# PERSEUS.net
KiCad netlist of a schematic drawn in Altium Designer
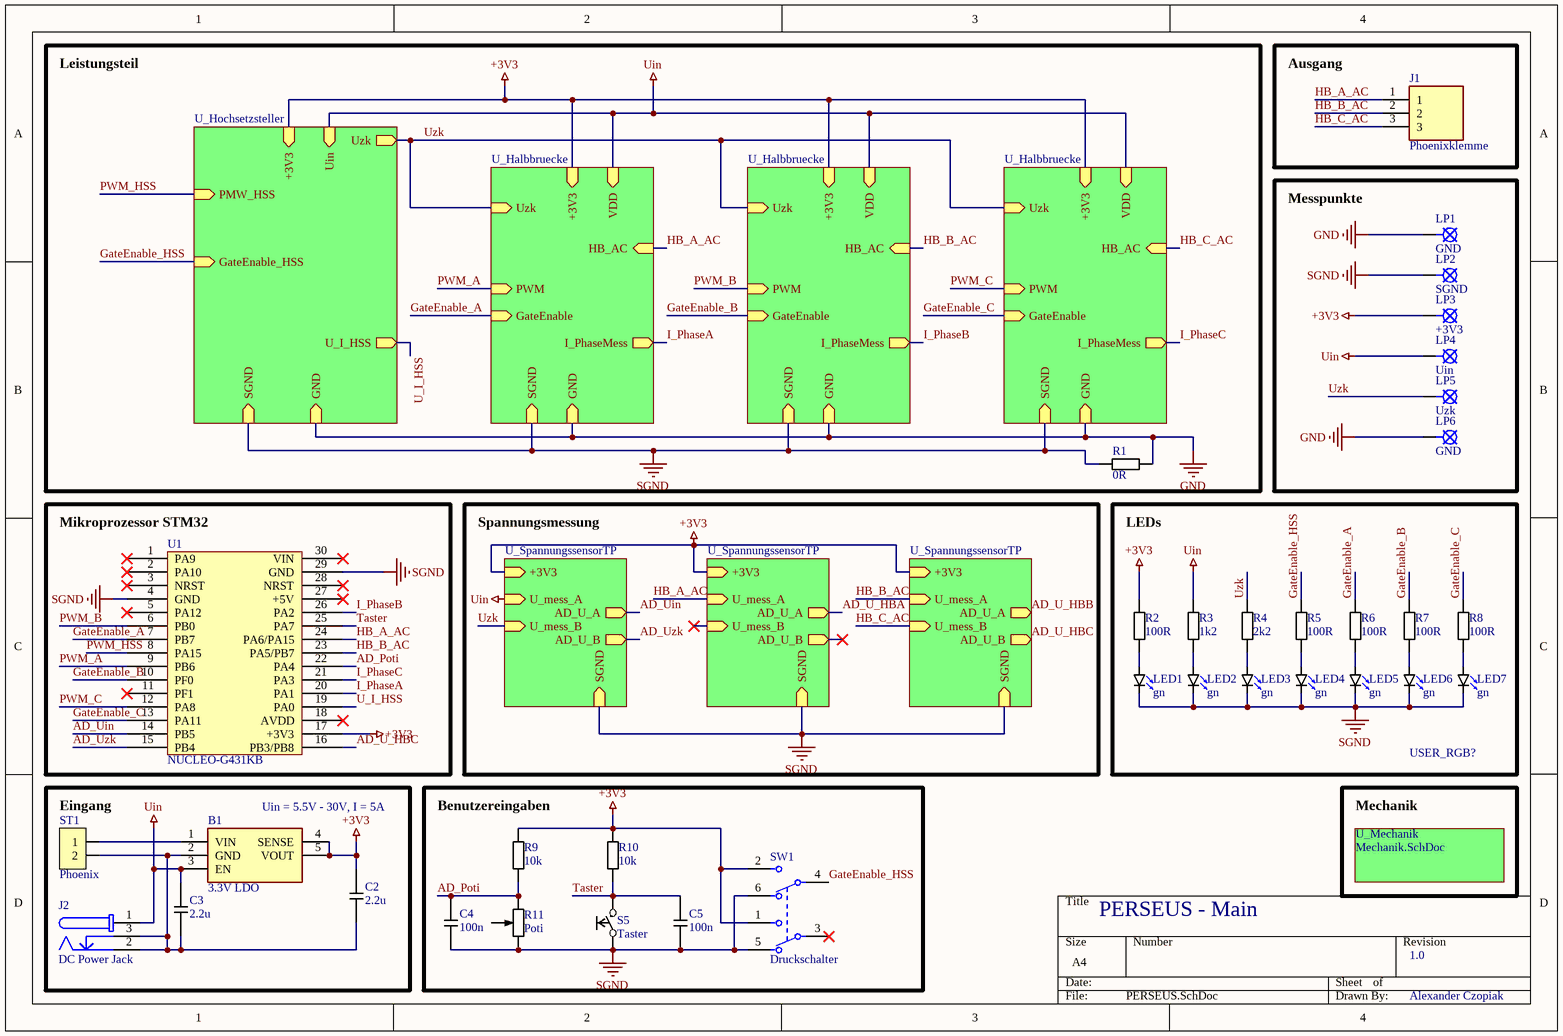
[diagram p0: PERSEUS.SchDoc]

(export (version "E")
  (design (tool "Eeschema 10.0.6"))
  (components
    (comp (ref "B1")
      (value "3.3V LDO")
      (footprint "SOT95P280X100-5N")
      (description "40V, 200mA, Low Noise, CMOS LDO Linear Regulator, ADPL44002AUJZ-3.3-R7")
      (fields
        (field (name "MOUSER PART NUMBER") "584-PL44002AUJZ33R7")
        (field (name "MANUFACTURER_PART_NUMBER") "ADPL44002AUJZ-3.3-R7")
      )
      (libsource (lib "PERSEUS_Parts") (part "Spannungsregler"))
    )
    (comp (ref "C2")
      (value "2.2u")
      (footprint "1206_C")
      (description "Min 2.2uF")
      (libsource (lib "HSLS_Parts") (part "CAP"))
    )
    (comp (ref "C3")
      (value "2.2u")
      (footprint "1206_C")
      (description "Min 2.2uF")
      (libsource (lib "HSLS_Parts") (part "CAP"))
    )
    (comp (ref "C4")
      (value "100n")
      (footprint "1206_C")
      (description "Kondensator (ohne Polarität)")
      (libsource (lib "HSLS_Parts") (part "CAP"))
    )
    (comp (ref "C5")
      (value "100n")
      (footprint "1206_C")
      (description "Kondensator (ohne Polarität)")
      (libsource (lib "HSLS_Parts") (part "CAP"))
    )
    (comp (ref "J1")
      (value "Phoenixklemme")
      (footprint "Phoenix_3er")
      (description "Phoenix: Fixed Terminal Blocks 3P 7.5mm GMKDS 1,5/ 3")
      (fields
        (field (name "MANUFACTURER_PART_NUMBER") "1717033")
        (field (name "MOUSER PART NUMBER") "651-1717033")
      )
      (libsource (lib "PERSEUS_Parts") (part "Leiterbahnklemme"))
    )
    (comp (ref "J2")
      (value "DC Power Jack")
      (footprint "694106301002")
      (libsource (lib "Altium Content Vault") (part "DC Power Jack"))
    )
    (comp (ref "LED1")
      (value "gn")
      (footprint "0805_DI_gr")
      (description "LED SMD 0805 (gruen)")
      (libsource (lib "HSLS_Parts") (part "LED SMD 0805"))
    )
    (comp (ref "LED2")
      (value "gn")
      (footprint "0805_DI_gr")
      (description "LED SMD 0805 (gruen)")
      (libsource (lib "HSLS_Parts") (part "LED SMD 0805"))
    )
    (comp (ref "LED3")
      (value "gn")
      (footprint "0805_DI_gr")
      (description "LED SMD 0805 (gruen)")
      (libsource (lib "HSLS_Parts") (part "LED SMD 0805"))
    )
    (comp (ref "LED4")
      (value "gn")
      (footprint "0805_DI_gr")
      (description "LED SMD 0805 (gruen)")
      (libsource (lib "HSLS_Parts") (part "LED SMD 0805"))
    )
    (comp (ref "LED5")
      (value "gn")
      (footprint "0805_DI_gr")
      (description "LED SMD 0805 (gruen)")
      (libsource (lib "HSLS_Parts") (part "LED SMD 0805"))
    )
    (comp (ref "LED6")
      (value "gn")
      (footprint "0805_DI_gr")
      (description "LED SMD 0805 (gruen)")
      (libsource (lib "HSLS_Parts") (part "LED SMD 0805"))
    )
    (comp (ref "LED7")
      (value "gn")
      (footprint "0805_DI_gr")
      (description "LED SMD 0805 (gruen)")
      (libsource (lib "HSLS_Parts") (part "LED SMD 0805"))
    )
    (comp (ref "LP1") (value "GND") (footprint "LP1") (libsource (lib "HSLS_Parts") (part "LP")))
    (comp (ref "LP2") (value "SGND") (footprint "LP1") (libsource (lib "HSLS_Parts") (part "LP")))
    (comp (ref "LP3") (value "+3V3") (footprint "LP1") (libsource (lib "HSLS_Parts") (part "LP")))
    (comp (ref "LP4") (value "Uin") (footprint "LP1") (libsource (lib "HSLS_Parts") (part "LP")))
    (comp (ref "LP5") (value "Uzk") (footprint "LP1") (libsource (lib "HSLS_Parts") (part "LP")))
    (comp (ref "LP6") (value "GND") (footprint "LP1") (libsource (lib "HSLS_Parts") (part "LP")))
    (comp (ref "R1")
      (value "0R")
      (footprint "1206_R")
      (description "LED Vorwiderstand: Min 65 Ohm, Berechnet für 3.3V, 2V Spannungsabfall, 20mA Strom")
      (libsource (lib "") (part "WIDERSTAND_1"))
    )
    (comp (ref "R2")
      (value "100R")
      (footprint "1206_R")
      (description "LED Vorwiderstand: Min 65 Ohm, Berechnet für 3.3V, 2V Spannungsabfall, 20mA Strom")
      (libsource (lib "HSLS_Parts") (part "WIDERSTAND"))
    )
    (comp (ref "R3")
      (value "1k2")
      (footprint "1206_R")
      (description "LED Vorwiderstand: Min 1.4 kOhm Berechnet für 30V Uin und 2 V Spannungsabfall und If=20mA")
      (libsource (lib "HSLS_Parts") (part "WIDERSTAND"))
    )
    (comp (ref "R4")
      (value "2k2")
      (footprint "1206_R")
      (description "Widerstand")
      (libsource (lib "HSLS_Parts") (part "WIDERSTAND"))
    )
    (comp (ref "R5")
      (value "100R")
      (footprint "1206_R")
      (description "Widerstand")
      (libsource (lib "HSLS_Parts") (part "WIDERSTAND"))
    )
    (comp (ref "R6")
      (value "100R")
      (footprint "1206_R")
      (description "Widerstand")
      (libsource (lib "HSLS_Parts") (part "WIDERSTAND"))
    )
    (comp (ref "R7")
      (value "100R")
      (footprint "1206_R")
      (description "LED Vorwiderstand: Min 65 Ohm, Berechnet für 3.3V, 2V Spannungsabfall, 20mA Strom")
      (libsource (lib "HSLS_Parts") (part "WIDERSTAND"))
    )
    (comp (ref "R8")
      (value "100R")
      (footprint "1206_R")
      (description "LED Vorwiderstand: Min 65 Ohm, Berechnet für 3.3V, 2V Spannungsabfall, 20mA Strom")
      (libsource (lib "HSLS_Parts") (part "WIDERSTAND"))
    )
    (comp (ref "R9")
      (value "10k")
      (footprint "1206_R")
      (description "LED Vorwiderstand: Min 1.4 kOhm Berechnet für 30V Uin und 2 V Spannungsabfall und If=20mA")
      (libsource (lib "HSLS_Parts") (part "WIDERSTAND"))
    )
    (comp (ref "R10")
      (value "10k")
      (footprint "1206_R")
      (description "LED Vorwiderstand: Min 1.4 kOhm Berechnet für 30V Uin und 2 V Spannungsabfall und If=20mA")
      (libsource (lib "HSLS_Parts") (part "WIDERSTAND"))
    )
    (comp (ref "R11")
      (value "Poti")
      (footprint "POT_T607_3D")
      (description "Widerstand")
      (libsource (lib "HSLS_Parts") (part "POT"))
    )
    (comp (ref "S5")
      (value "Taster")
      (footprint "TASTERSMD_3D")
      (libsource (lib "HSLS_Parts") (part "TASTER-SMD"))
    )
    (comp (ref "ST1")
      (value "Phoenix")
      (footprint "MKDS 1,5/ 2")
      (description "Phönix-Klemme")
      (libsource (lib "HSLS_Parts") (part "CONN02"))
    )
    (comp (ref "SW1")
      (value "Druckschalter")
      (footprint "FP-ESB-33133-MFG")
      (description "SWITCH PUSH DPDT 0.2A 14V")
      (libsource (lib "Altium Content Vault") (part "c2a961280ed03fe855f28de6b03a4b6"))
    )
    (comp (ref "U1")
      (value "NUCLEO-G431KB")
      (footprint "NUCLEO-G431KB")
      (libsource (lib "PERSEUS_Parts") (part "NUCLEO-G431KB"))
    )
  )
  (nets
    (net (code "1") (name "+3V3") (class "Default")
      (node (ref "B1") (pin "4") (pinfunction "SENSE_4") (pintype "passive"))
      (node (ref "B1") (pin "5") (pinfunction "VOUT_5") (pintype "passive"))
      (node (ref "C2") (pin "2") (pinfunction "2_2") (pintype "passive"))
      (node (ref "LP3") (pin "1") (pinfunction "1_1") (pintype "passive"))
      (node (ref "R10") (pin "2") (pinfunction "2_2") (pintype "passive"))
      (node (ref "R2") (pin "2") (pinfunction "2_2") (pintype "passive"))
      (node (ref "R9") (pin "2") (pinfunction "2_2") (pintype "passive"))
      (node (ref "SW1") (pin "1") (pinfunction "1_NO_1") (pintype "passive"))
      (node (ref "SW1") (pin "2") (pinfunction "2_NO_2") (pintype "passive"))
      (node (ref "U1") (pin "17") (pinfunction "+3V3_17") (pintype "passive"))
    )
    (net (code "3") (name "/AD_Poti") (class "Default")
      (node (ref "C4") (pin "2") (pinfunction "2_2") (pintype "passive"))
      (node (ref "R11") (pin "2") (pintype "passive"))
      (node (ref "R9") (pin "1") (pinfunction "1_1") (pintype "passive"))
      (node (ref "U1") (pin "22") (pinfunction "PA4_22") (pintype "passive"))
    )
    (net (code "6") (name "/AD_U_HBC") (class "Default")
      (node (ref "U1") (pin "16") (pinfunction "PB3/PB8_16") (pintype "passive"))
    )
    (net (code "7") (name "/AD_Uin") (class "Default")
      (node (ref "U1") (pin "14") (pinfunction "PB5_14") (pintype "passive"))
    )
    (net (code "8") (name "/AD_Uzk") (class "Default")
      (node (ref "U1") (pin "15") (pinfunction "PB4_15") (pintype "passive"))
    )
    (net (code "9") (name "/GateEnable_A") (class "Default")
      (node (ref "R6") (pin "2") (pinfunction "2_2") (pintype "passive"))
      (node (ref "U1") (pin "7") (pinfunction "PB7_7") (pintype "passive"))
    )
    (net (code "10") (name "/GateEnable_B") (class "Default")
      (node (ref "R7") (pin "2") (pinfunction "2_2") (pintype "passive"))
      (node (ref "U1") (pin "10") (pinfunction "PF0_10") (pintype "passive"))
    )
    (net (code "11") (name "/GateEnable_C") (class "Default")
      (node (ref "R8") (pin "2") (pinfunction "2_2") (pintype "passive"))
      (node (ref "U1") (pin "13") (pinfunction "PA11_13") (pintype "passive"))
    )
    (net (code "12") (name "/GateEnable_HSS") (class "Default")
      (node (ref "R5") (pin "2") (pinfunction "2_2") (pintype "passive"))
      (node (ref "SW1") (pin "4") (pinfunction "2_C_4") (pintype "passive"))
    )
    (net (code "13") (name "/HB_A_AC") (class "Default")
      (node (ref "J1") (pin "1") (pinfunction "1_1") (pintype "passive"))
      (node (ref "U1") (pin "24") (pinfunction "PA6/PA15_24") (pintype "passive"))
    )
    (net (code "14") (name "/HB_B_AC") (class "Default")
      (node (ref "J1") (pin "2") (pinfunction "2_2") (pintype "passive"))
      (node (ref "U1") (pin "23") (pinfunction "PA5/PB7_23") (pintype "passive"))
    )
    (net (code "15") (name "/HB_C_AC") (class "Default")
      (node (ref "J1") (pin "3") (pinfunction "3_3") (pintype "passive"))
    )
    (net (code "16") (name "/I_PhaseA") (class "Default")
      (node (ref "U1") (pin "20") (pinfunction "PA1_20") (pintype "passive"))
    )
    (net (code "17") (name "/I_PhaseB") (class "Default")
      (node (ref "U1") (pin "26") (pinfunction "PA2_26") (pintype "passive"))
    )
    (net (code "18") (name "/I_PhaseC") (class "Default")
      (node (ref "U1") (pin "21") (pinfunction "PA3_21") (pintype "passive"))
    )
    (net (code "19") (name "/PWM_A") (class "Default")
      (node (ref "U1") (pin "9") (pinfunction "PB6_9") (pintype "passive"))
    )
    (net (code "20") (name "/PWM_B") (class "Default")
      (node (ref "U1") (pin "6") (pinfunction "PB0_6") (pintype "passive"))
    )
    (net (code "21") (name "/PWM_C") (class "Default")
      (node (ref "U1") (pin "12") (pinfunction "PA8_12") (pintype "passive"))
    )
    (net (code "22") (name "/PWM_HSS") (class "Default")
      (node (ref "U1") (pin "8") (pinfunction "PA15_8") (pintype "passive"))
    )
    (net (code "23") (name "/Taster") (class "Default")
      (node (ref "C5") (pin "2") (pinfunction "2_2") (pintype "passive"))
      (node (ref "R10") (pin "1") (pinfunction "1_1") (pintype "passive"))
      (node (ref "S5") (pin "1") (pinfunction "1_1") (pintype "passive"))
      (node (ref "U1") (pin "25") (pinfunction "PA7_25") (pintype "passive"))
    )
    (net (code "24") (name "/U_I_HSS") (class "Default")
      (node (ref "U1") (pin "19") (pinfunction "PA0_19") (pintype "passive"))
    )
    (net (code "26") (name "/Uzk") (class "Default")
      (node (ref "LP5") (pin "1") (pinfunction "1_1") (pintype "passive"))
      (node (ref "R4") (pin "2") (pinfunction "2_2") (pintype "passive"))
    )
    (net (code "27") (name "GND") (class "Default")
      (node (ref "LP1") (pin "1") (pinfunction "1_1") (pintype "passive"))
      (node (ref "LP6") (pin "1") (pinfunction "1_1") (pintype "passive"))
      (node (ref "R1") (pin "1") (pinfunction "1_1") (pintype "passive"))
    )
    (net (code "28") (name "Net-(B1-GND)") (class "Default")
      (node (ref "B1") (pin "2") (pinfunction "GND_2") (pintype "passive"))
      (node (ref "C2") (pin "1") (pinfunction "1_1") (pintype "passive"))
      (node (ref "C3") (pin "1") (pinfunction "1_1") (pintype "passive"))
      (node (ref "J2") (pin "2") (pinfunction "2_2") (pintype "passive"))
      (node (ref "J2") (pin "3") (pinfunction "3_3") (pintype "passive"))
      (node (ref "ST1") (pin "2") (pinfunction "2_2") (pintype "passive"))
    )
    (net (code "29") (name "Net-(B1-VIN)") (class "Default")
      (node (ref "B1") (pin "1") (pinfunction "VIN_1") (pintype "passive"))
      (node (ref "ST1") (pin "1") (pinfunction "1_1") (pintype "passive"))
    )
    (net (code "30") (name "Net-(LED1-A)") (class "Default")
      (node (ref "LED1") (pin "1") (pinfunction "A_1") (pintype "passive"))
      (node (ref "R2") (pin "1") (pinfunction "1_1") (pintype "passive"))
    )
    (net (code "31") (name "Net-(LED2-A)") (class "Default")
      (node (ref "LED2") (pin "1") (pinfunction "A_1") (pintype "passive"))
      (node (ref "R3") (pin "1") (pinfunction "1_1") (pintype "passive"))
    )
    (net (code "32") (name "Net-(LED3-A)") (class "Default")
      (node (ref "LED3") (pin "1") (pinfunction "A_1") (pintype "passive"))
      (node (ref "R4") (pin "1") (pinfunction "1_1") (pintype "passive"))
    )
    (net (code "33") (name "Net-(LED4-A)") (class "Default")
      (node (ref "LED4") (pin "1") (pinfunction "A_1") (pintype "passive"))
      (node (ref "R5") (pin "1") (pinfunction "1_1") (pintype "passive"))
    )
    (net (code "34") (name "Net-(LED5-A)") (class "Default")
      (node (ref "LED5") (pin "1") (pinfunction "A_1") (pintype "passive"))
      (node (ref "R6") (pin "1") (pinfunction "1_1") (pintype "passive"))
    )
    (net (code "35") (name "Net-(LED6-A)") (class "Default")
      (node (ref "LED6") (pin "1") (pinfunction "A_1") (pintype "passive"))
      (node (ref "R7") (pin "1") (pinfunction "1_1") (pintype "passive"))
    )
    (net (code "36") (name "Net-(LED7-A)") (class "Default")
      (node (ref "LED7") (pin "1") (pinfunction "A_1") (pintype "passive"))
      (node (ref "R8") (pin "1") (pinfunction "1_1") (pintype "passive"))
    )
    (net (code "37") (name "SGND") (class "Default")
      (node (ref "C4") (pin "1") (pinfunction "1_1") (pintype "passive"))
      (node (ref "C5") (pin "1") (pinfunction "1_1") (pintype "passive"))
      (node (ref "LED1") (pin "2") (pinfunction "K_2") (pintype "passive"))
      (node (ref "LED2") (pin "2") (pinfunction "K_2") (pintype "passive"))
      (node (ref "LED3") (pin "2") (pinfunction "K_2") (pintype "passive"))
      (node (ref "LED4") (pin "2") (pinfunction "K_2") (pintype "passive"))
      (node (ref "LED5") (pin "2") (pinfunction "K_2") (pintype "passive"))
      (node (ref "LED6") (pin "2") (pinfunction "K_2") (pintype "passive"))
      (node (ref "LED7") (pin "2") (pinfunction "K_2") (pintype "passive"))
      (node (ref "LP2") (pin "1") (pinfunction "1_1") (pintype "passive"))
      (node (ref "R1") (pin "2") (pinfunction "2_2") (pintype "passive"))
      (node (ref "R11") (pin "1") (pintype "passive"))
      (node (ref "S5") (pin "2") (pinfunction "2_2") (pintype "passive"))
      (node (ref "SW1") (pin "5") (pinfunction "1_NC_5") (pintype "passive"))
      (node (ref "SW1") (pin "6") (pinfunction "2_NC_6") (pintype "passive"))
      (node (ref "U1") (pin "29") (pinfunction "GND_29") (pintype "passive"))
      (node (ref "U1") (pin "4") (pinfunction "GND_4") (pintype "passive"))
    )
    (net (code "38") (name "Uin") (class "Default")
      (node (ref "B1") (pin "3") (pinfunction "EN_3") (pintype "passive"))
      (node (ref "C3") (pin "2") (pinfunction "2_2") (pintype "passive"))
      (node (ref "J2") (pin "1") (pinfunction "1_1") (pintype "passive"))
      (node (ref "LP4") (pin "1") (pinfunction "1_1") (pintype "passive"))
      (node (ref "R3") (pin "2") (pinfunction "2_2") (pintype "passive"))
    )
    (net (code "39") (name "unconnected-(R11-Abgriff-PadW)") (class "Default")
      (node (ref "R11") (pin "W") (pinfunction "Abgriff_W") (pintype "passive"))
    )
    (net (code "40") (name "unconnected-(SW1-1_C-Pad3)") (class "Default")
      (node (ref "SW1") (pin "3") (pinfunction "1_C_3") (pintype "passive+no_connect"))
    )
    (net (code "41") (name "unconnected-(U1-+5V-Pad27)") (class "Default")
      (node (ref "U1") (pin "27") (pinfunction "+5V_27") (pintype "passive+no_connect"))
    )
    (net (code "42") (name "unconnected-(U1-AVDD-Pad18)") (class "Default")
      (node (ref "U1") (pin "18") (pinfunction "AVDD_18") (pintype "passive+no_connect"))
    )
    (net (code "43") (name "unconnected-(U1-NRST-Pad3)") (class "Default")
      (node (ref "U1") (pin "3") (pinfunction "NRST_3") (pintype "passive+no_connect"))
    )
    (net (code "44") (name "unconnected-(U1-NRST-Pad28)") (class "Default")
      (node (ref "U1") (pin "28") (pinfunction "NRST_28") (pintype "passive+no_connect"))
    )
    (net (code "45") (name "unconnected-(U1-PA9-Pad1)") (class "Default")
      (node (ref "U1") (pin "1") (pinfunction "PA9_1") (pintype "passive+no_connect"))
    )
    (net (code "46") (name "unconnected-(U1-PA10-Pad2)") (class "Default")
      (node (ref "U1") (pin "2") (pinfunction "PA10_2") (pintype "passive+no_connect"))
    )
    (net (code "47") (name "unconnected-(U1-PA12-Pad5)") (class "Default")
      (node (ref "U1") (pin "5") (pinfunction "PA12_5") (pintype "passive+no_connect"))
    )
    (net (code "48") (name "unconnected-(U1-PF1-Pad11)") (class "Default")
      (node (ref "U1") (pin "11") (pinfunction "PF1_11") (pintype "passive+no_connect"))
    )
    (net (code "49") (name "unconnected-(U1-VIN-Pad30)") (class "Default")
      (node (ref "U1") (pin "30") (pinfunction "VIN_30") (pintype "passive+no_connect"))
    )
  )
)
